# Photodiode_AFE.net
KiCad netlist of a schematic drawn in Altium Designer
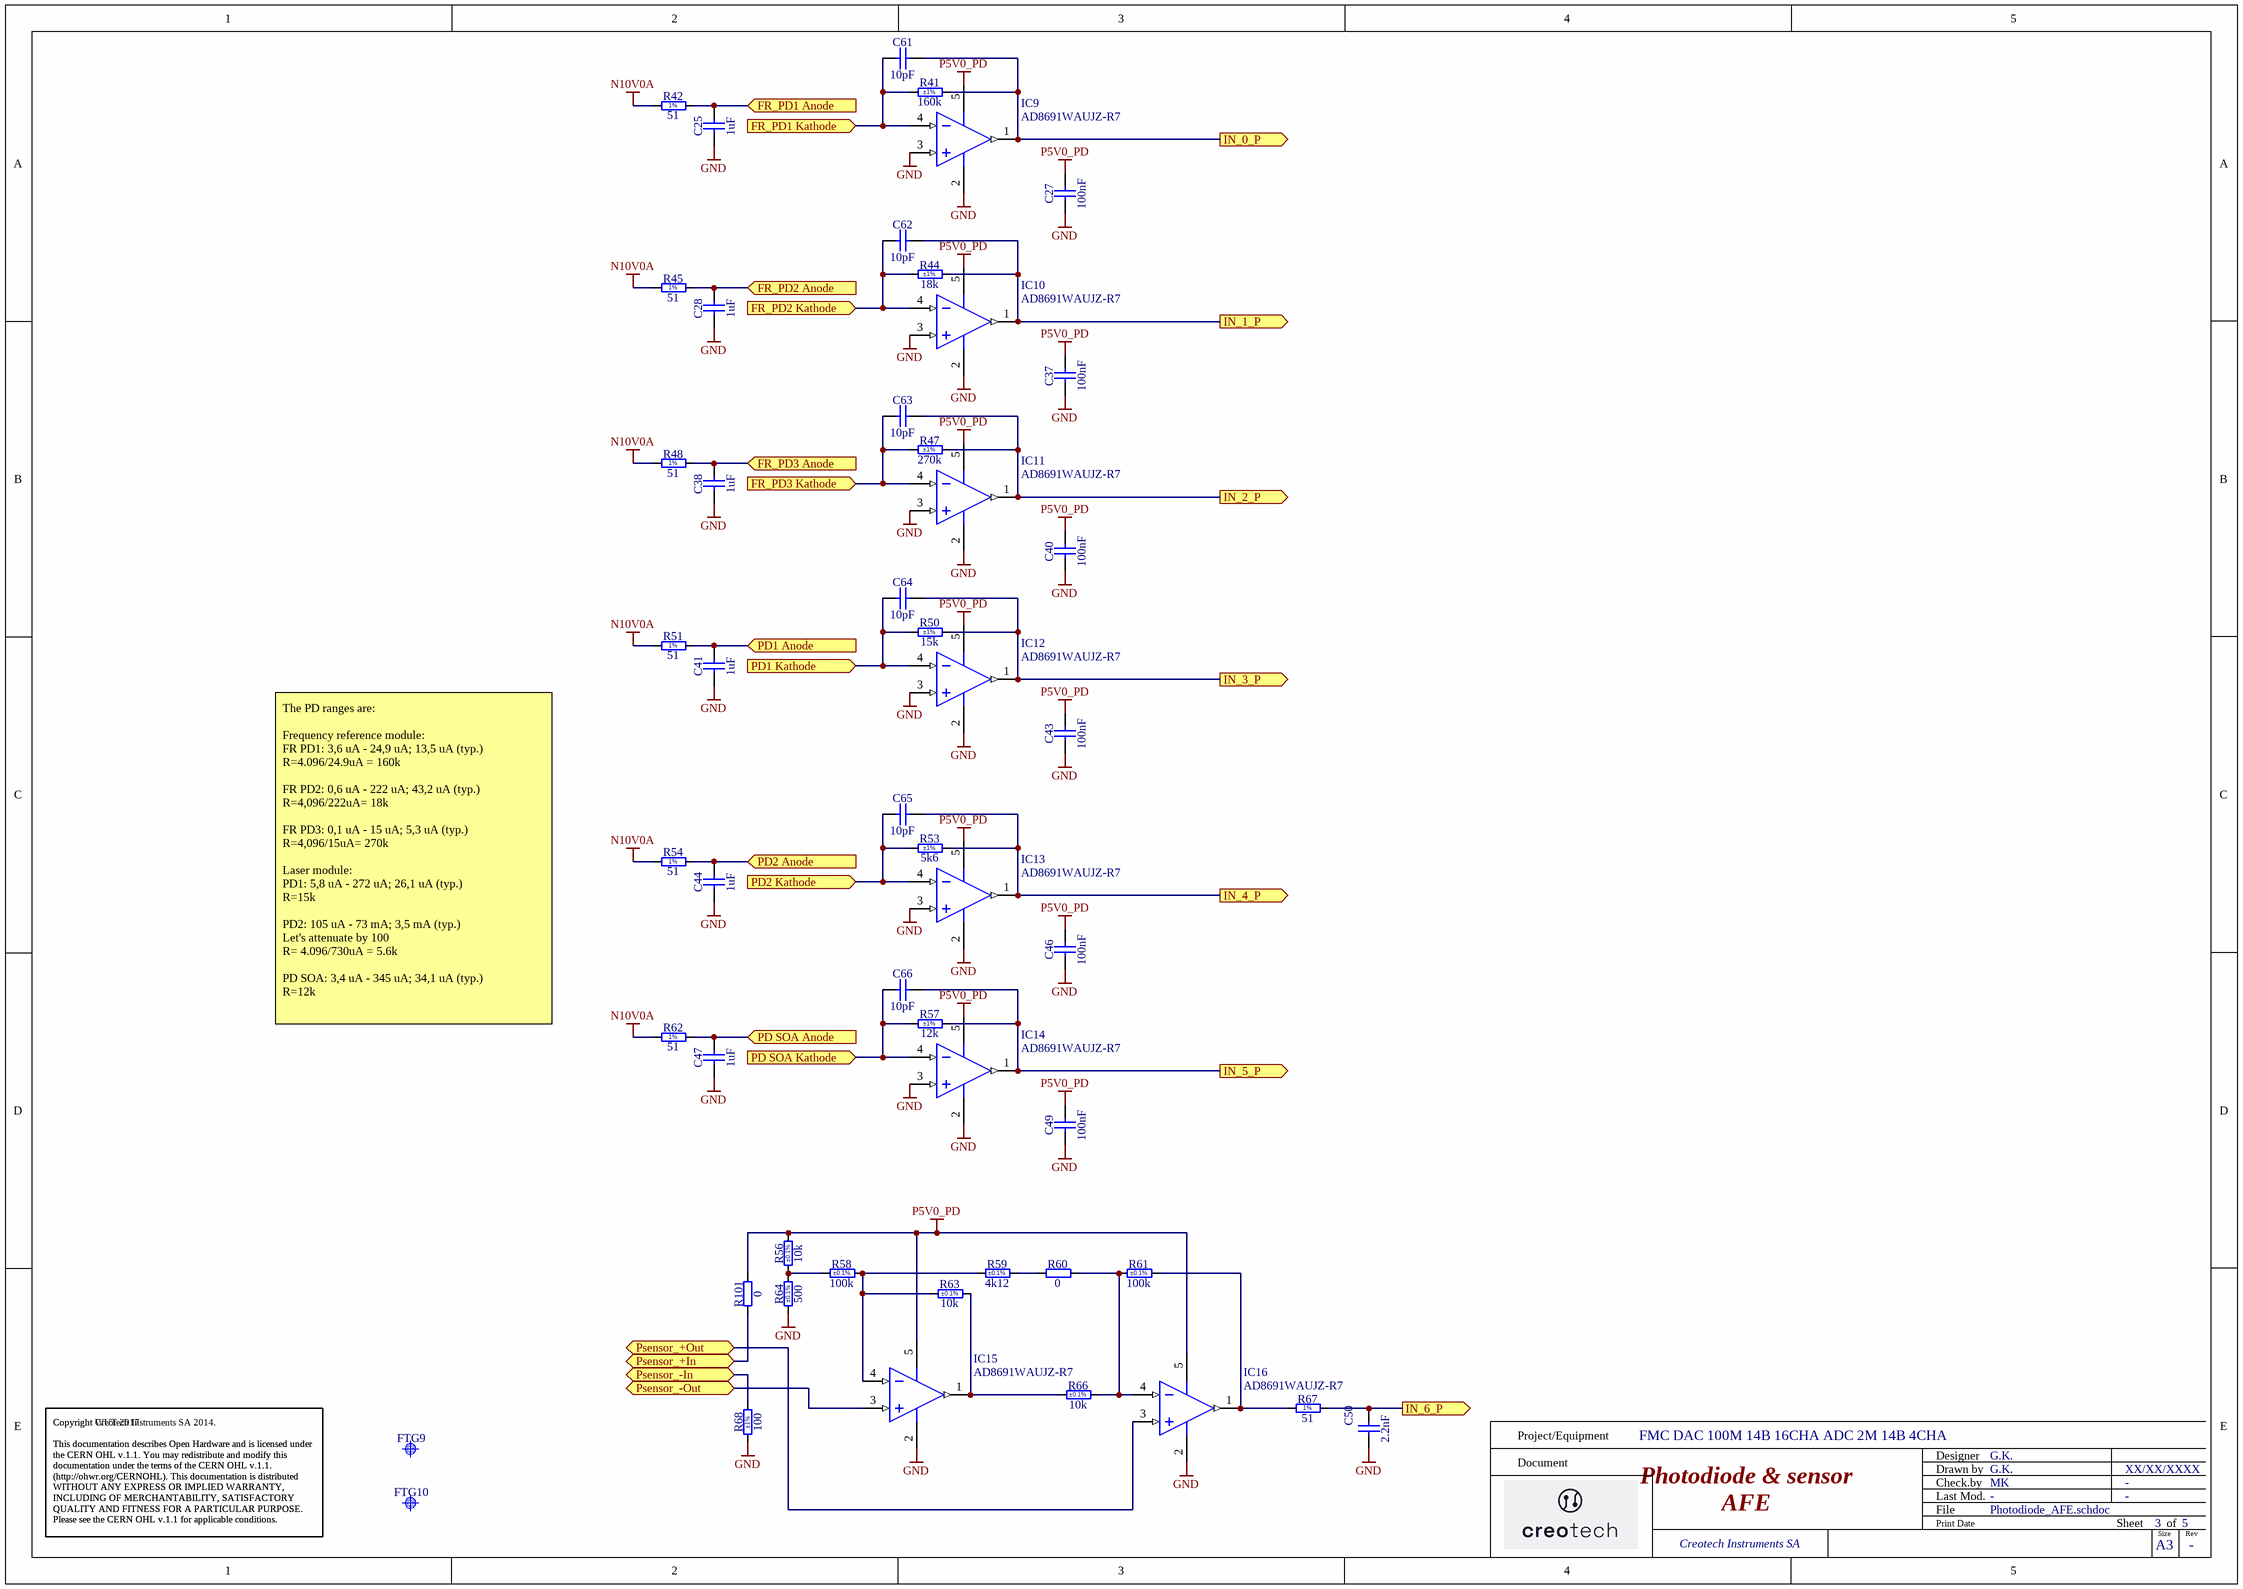
[diagram p0: Photodiode_AFE.schdoc]

(export (version "E")
  (design (tool "Eeschema 10.0.6"))
  (components
    (comp (ref "C25")
      (value "1uF")
      (footprint "CAPC1005X55N")
      (description "Non-polarised capacitor")
      (fields
        (field (name "PART NUMBER") "CC0402_1UF_16V_10%_X5R")
        (field (name "VOLTAGE") "16V")
        (field (name "AUTHOR") "CERN DEM JLC")
      )
      (libsource (lib "Capacitors") (part "Capacitor - non polarized"))
    )
    (comp (ref "C27")
      (value "100nF")
      (footprint "CAPC1005X55N")
      (description "Non-polarised capacitor")
      (fields
        (field (name "PART NUMBER") "CC0402_100NF_16V_10%_X5R")
        (field (name "VOLTAGE") "16V")
        (field (name "AUTHOR") "CERN DEM JLC")
      )
      (libsource (lib "Capacitors") (part "Capacitor - non polarized"))
    )
    (comp (ref "C28")
      (value "1uF")
      (footprint "CAPC1005X55N")
      (description "Non-polarised capacitor")
      (fields
        (field (name "PART NUMBER") "CC0402_1UF_16V_10%_X5R")
        (field (name "VOLTAGE") "16V")
        (field (name "AUTHOR") "CERN DEM JLC")
      )
      (libsource (lib "Capacitors") (part "Capacitor - non polarized"))
    )
    (comp (ref "C37")
      (value "100nF")
      (footprint "CAPC1005X55N")
      (description "Non-polarised capacitor")
      (fields
        (field (name "PART NUMBER") "CC0402_100NF_16V_10%_X5R")
        (field (name "VOLTAGE") "16V")
        (field (name "AUTHOR") "CERN DEM JLC")
      )
      (libsource (lib "Capacitors") (part "Capacitor - non polarized"))
    )
    (comp (ref "C38")
      (value "1uF")
      (footprint "CAPC1005X55N")
      (description "Non-polarised capacitor")
      (fields
        (field (name "PART NUMBER") "CC0402_1UF_16V_10%_X5R")
        (field (name "VOLTAGE") "16V")
        (field (name "AUTHOR") "CERN DEM JLC")
      )
      (libsource (lib "Capacitors") (part "Capacitor - non polarized"))
    )
    (comp (ref "C40")
      (value "100nF")
      (footprint "CAPC1005X55N")
      (description "Non-polarised capacitor")
      (fields
        (field (name "PART NUMBER") "CC0402_100NF_16V_10%_X5R")
        (field (name "VOLTAGE") "16V")
        (field (name "AUTHOR") "CERN DEM JLC")
      )
      (libsource (lib "Capacitors") (part "Capacitor - non polarized"))
    )
    (comp (ref "C41")
      (value "1uF")
      (footprint "CAPC1005X55N")
      (description "Non-polarised capacitor")
      (fields
        (field (name "PART NUMBER") "CC0402_1UF_16V_10%_X5R")
        (field (name "VOLTAGE") "16V")
        (field (name "AUTHOR") "CERN DEM JLC")
      )
      (libsource (lib "Capacitors") (part "Capacitor - non polarized"))
    )
    (comp (ref "C43")
      (value "100nF")
      (footprint "CAPC1005X55N")
      (description "Non-polarised capacitor")
      (fields
        (field (name "PART NUMBER") "CC0402_100NF_16V_10%_X5R")
        (field (name "VOLTAGE") "16V")
        (field (name "AUTHOR") "CERN DEM JLC")
      )
      (libsource (lib "Capacitors") (part "Capacitor - non polarized"))
    )
    (comp (ref "C44")
      (value "1uF")
      (footprint "CAPC1005X55N")
      (description "Non-polarised capacitor")
      (fields
        (field (name "PART NUMBER") "CC0402_1UF_16V_10%_X5R")
        (field (name "VOLTAGE") "16V")
        (field (name "AUTHOR") "CERN DEM JLC")
      )
      (libsource (lib "Capacitors") (part "Capacitor - non polarized"))
    )
    (comp (ref "C46")
      (value "100nF")
      (footprint "CAPC1005X55N")
      (description "Non-polarised capacitor")
      (fields
        (field (name "PART NUMBER") "CC0402_100NF_16V_10%_X5R")
        (field (name "VOLTAGE") "16V")
        (field (name "AUTHOR") "CERN DEM JLC")
      )
      (libsource (lib "Capacitors") (part "Capacitor - non polarized"))
    )
    (comp (ref "C47")
      (value "1uF")
      (footprint "CAPC1005X55N")
      (description "Non-polarised capacitor")
      (fields
        (field (name "PART NUMBER") "CC0402_1UF_16V_10%_X5R")
        (field (name "VOLTAGE") "16V")
        (field (name "AUTHOR") "CERN DEM JLC")
      )
      (libsource (lib "Capacitors") (part "Capacitor - non polarized"))
    )
    (comp (ref "C49")
      (value "100nF")
      (footprint "CAPC1005X55N")
      (description "Non-polarised capacitor")
      (fields
        (field (name "PART NUMBER") "CC0402_100NF_16V_10%_X5R")
        (field (name "VOLTAGE") "16V")
        (field (name "AUTHOR") "CERN DEM JLC")
      )
      (libsource (lib "Capacitors") (part "Capacitor - non polarized"))
    )
    (comp (ref "C50")
      (value "2.2nF")
      (footprint "CAPC2013X100N")
      (description "Non-polarised capacitor")
      (fields
        (field (name "PART NUMBER") "CC0805_2.2NF_25V_1%_C0G")
        (field (name "VOLTAGE") "25V")
        (field (name "AUTHOR") "CERN DEM JLC")
      )
      (libsource (lib "Capacitors") (part "Capacitor - non polarized"))
    )
    (comp (ref "C61")
      (value "10pF")
      (footprint "CAPC1005X55N")
      (description "Non-polarised capacitor")
      (fields
        (field (name "PART NUMBER") "CC0402_10PF_50V_5%_C0G")
        (field (name "VOLTAGE") "50V")
        (field (name "AUTHOR") "CERN DEM JLC")
      )
      (libsource (lib "Capacitors") (part "Capacitor - non polarized"))
    )
    (comp (ref "C62")
      (value "10pF")
      (footprint "CAPC1005X55N")
      (description "Non-polarised capacitor")
      (fields
        (field (name "PART NUMBER") "CC0402_10PF_50V_5%_C0G")
        (field (name "VOLTAGE") "50V")
        (field (name "AUTHOR") "CERN DEM JLC")
      )
      (libsource (lib "Capacitors") (part "Capacitor - non polarized"))
    )
    (comp (ref "C63")
      (value "10pF")
      (footprint "CAPC1005X55N")
      (description "Non-polarised capacitor")
      (fields
        (field (name "PART NUMBER") "CC0402_10PF_50V_5%_C0G")
        (field (name "VOLTAGE") "50V")
        (field (name "AUTHOR") "CERN DEM JLC")
      )
      (libsource (lib "Capacitors") (part "Capacitor - non polarized"))
    )
    (comp (ref "C64")
      (value "10pF")
      (footprint "CAPC1005X55N")
      (description "Non-polarised capacitor")
      (fields
        (field (name "PART NUMBER") "CC0402_10PF_50V_5%_C0G")
        (field (name "VOLTAGE") "50V")
        (field (name "AUTHOR") "CERN DEM JLC")
      )
      (libsource (lib "Capacitors") (part "Capacitor - non polarized"))
    )
    (comp (ref "C65")
      (value "10pF")
      (footprint "CAPC1005X55N")
      (description "Non-polarised capacitor")
      (fields
        (field (name "PART NUMBER") "CC0402_10PF_50V_5%_C0G")
        (field (name "VOLTAGE") "50V")
        (field (name "AUTHOR") "CERN DEM JLC")
      )
      (libsource (lib "Capacitors") (part "Capacitor - non polarized"))
    )
    (comp (ref "C66")
      (value "10pF")
      (footprint "CAPC1005X55N")
      (description "Non-polarised capacitor")
      (fields
        (field (name "PART NUMBER") "CC0402_10PF_50V_5%_C0G")
        (field (name "VOLTAGE") "50V")
        (field (name "AUTHOR") "CERN DEM JLC")
      )
      (libsource (lib "Capacitors") (part "Capacitor - non polarized"))
    )
    (comp (ref "FTG9")
      (value "Use only in PCB")
      (footprint "FIDUCIAL_TOP_C100-200")
      (description "Fiducial Target")
      (fields (field (name "PART NUMBER") "FIDUCIAL_TARGET_C100-200") (field (name "AUTHOR") "CERN DEM JLC"))
      (libsource (lib "Eletro-mechanical") (part "Fiducial Target"))
    )
    (comp (ref "FTG10")
      (value "Use only in PCB")
      (footprint "FIDUCIAL_TOP_S100-200")
      (description "Fiducial Target")
      (fields (field (name "PART NUMBER") "FIDUCIAL_TARGET_S100-200") (field (name "AUTHOR") "CERN DEM JLC"))
      (libsource (lib "Eletro-mechanical") (part "Fiducial Target"))
    )
    (comp (ref "IC9")
      (value "AD8691WAUJZ-R7")
      (footprint "ADI-UJ-5_L")
      (fields (field (name "MANUFACTURER") "Analog Devices") (field (name "GENERIC PART NUMBER") "AD8691"))
      (libsource (lib "Altium Content Vault") (part "ADI-AD8605-CB-5_8691-UJ-5"))
    )
    (comp (ref "IC10")
      (value "AD8691WAUJZ-R7")
      (footprint "ADI-UJ-5_L")
      (fields (field (name "MANUFACTURER") "Analog Devices") (field (name "GENERIC PART NUMBER") "AD8691"))
      (libsource (lib "Altium Content Vault") (part "ADI-AD8605-CB-5_8691-UJ-5"))
    )
    (comp (ref "IC11")
      (value "AD8691WAUJZ-R7")
      (footprint "ADI-UJ-5_L")
      (fields (field (name "MANUFACTURER") "Analog Devices") (field (name "GENERIC PART NUMBER") "AD8691"))
      (libsource (lib "Altium Content Vault") (part "ADI-AD8605-CB-5_8691-UJ-5"))
    )
    (comp (ref "IC12")
      (value "AD8691WAUJZ-R7")
      (footprint "ADI-UJ-5_L")
      (fields (field (name "MANUFACTURER") "Analog Devices") (field (name "GENERIC PART NUMBER") "AD8691"))
      (libsource (lib "Altium Content Vault") (part "ADI-AD8605-CB-5_8691-UJ-5"))
    )
    (comp (ref "IC13")
      (value "AD8691WAUJZ-R7")
      (footprint "ADI-UJ-5_L")
      (fields (field (name "MANUFACTURER") "Analog Devices") (field (name "GENERIC PART NUMBER") "AD8691"))
      (libsource (lib "Altium Content Vault") (part "ADI-AD8605-CB-5_8691-UJ-5"))
    )
    (comp (ref "IC14")
      (value "AD8691WAUJZ-R7")
      (footprint "ADI-UJ-5_L")
      (fields (field (name "MANUFACTURER") "Analog Devices") (field (name "GENERIC PART NUMBER") "AD8691"))
      (libsource (lib "Altium Content Vault") (part "ADI-AD8605-CB-5_8691-UJ-5"))
    )
    (comp (ref "IC15")
      (value "AD8691WAUJZ-R7")
      (footprint "ADI-UJ-5_L")
      (fields (field (name "MANUFACTURER") "Analog Devices") (field (name "GENERIC PART NUMBER") "AD8691"))
      (libsource (lib "Altium Content Vault") (part "ADI-AD8605-CB-5_8691-UJ-5"))
    )
    (comp (ref "IC16")
      (value "AD8691WAUJZ-R7")
      (footprint "ADI-UJ-5_L")
      (fields (field (name "MANUFACTURER") "Analog Devices") (field (name "GENERIC PART NUMBER") "AD8691"))
      (libsource (lib "Altium Content Vault") (part "ADI-AD8605-CB-5_8691-UJ-5"))
    )
    (comp (ref "R41")
      (value "160k")
      (footprint "RESC1608X55N")
      (description "Resistor - 1%")
      (fields
        (field (name "TOLERANCE") "±1%")
        (field (name "PART NUMBER") "R0603_160K_1%_0.1W_100PPM")
        (field (name "POWER") "0.1W")
        (field (name "AUTHOR") "CERN DEM JLC")
      )
      (libsource (lib "") (part "Resistor - 1%_1"))
    )
    (comp (ref "R42")
      (value "51")
      (footprint "RESC1005X40N")
      (description "Resistor - 1%")
      (fields
        (field (name "PART NUMBER") "R0402_51R_1%_0.0625W_100PPM")
        (field (name "POWER") "0.0625W")
        (field (name "AUTHOR") "CERN DEM JLC")
      )
      (libsource (lib "Resistors") (part "Resistor - 1%"))
    )
    (comp (ref "R44")
      (value "18k")
      (footprint "RESC1608X55N")
      (description "Resistor - 1%")
      (fields
        (field (name "TOLERANCE") "±1%")
        (field (name "PART NUMBER") "R0603_18K_1%_0.1W_100PPM")
        (field (name "POWER") "0.1W")
        (field (name "AUTHOR") "CERN DEM JLC")
      )
      (libsource (lib "") (part "Resistor - 1%_1"))
    )
    (comp (ref "R45")
      (value "51")
      (footprint "RESC1005X40N")
      (description "Resistor - 1%")
      (fields
        (field (name "PART NUMBER") "R0402_51R_1%_0.0625W_100PPM")
        (field (name "POWER") "0.0625W")
        (field (name "AUTHOR") "CERN DEM JLC")
      )
      (libsource (lib "Resistors") (part "Resistor - 1%"))
    )
    (comp (ref "R47")
      (value "270k")
      (footprint "RESC1608X55N")
      (description "Resistor - 1%")
      (fields
        (field (name "TOLERANCE") "±1%")
        (field (name "PART NUMBER") "R0603_270K_1%_0.1W_100PPM")
        (field (name "POWER") "0.1W")
        (field (name "AUTHOR") "CERN DEM JLC")
      )
      (libsource (lib "") (part "Resistor - 1%_1"))
    )
    (comp (ref "R48")
      (value "51")
      (footprint "RESC1005X40N")
      (description "Resistor - 1%")
      (fields
        (field (name "PART NUMBER") "R0402_51R_1%_0.0625W_100PPM")
        (field (name "POWER") "0.0625W")
        (field (name "AUTHOR") "CERN DEM JLC")
      )
      (libsource (lib "Resistors") (part "Resistor - 1%"))
    )
    (comp (ref "R50")
      (value "15k")
      (footprint "RESC1608X55N")
      (description "Resistor - 1%")
      (fields
        (field (name "TOLERANCE") "±1%")
        (field (name "PART NUMBER") "R0603_15K_1%_0.1W_100PPM")
        (field (name "POWER") "0.1W")
        (field (name "AUTHOR") "CERN DEM JMW")
      )
      (libsource (lib "") (part "Resistor - 1%_1"))
    )
    (comp (ref "R51")
      (value "51")
      (footprint "RESC1005X40N")
      (description "Resistor - 1%")
      (fields
        (field (name "PART NUMBER") "R0402_51R_1%_0.0625W_100PPM")
        (field (name "POWER") "0.0625W")
        (field (name "AUTHOR") "CERN DEM JLC")
      )
      (libsource (lib "Resistors") (part "Resistor - 1%"))
    )
    (comp (ref "R53")
      (value "5k6")
      (footprint "RESC1608X55N")
      (description "Resistor - 1%")
      (fields
        (field (name "TOLERANCE") "±1%")
        (field (name "PART NUMBER") "R0603_5K6_1%_0.125W_100PPM")
        (field (name "POWER") "0.125W")
        (field (name "AUTHOR") "CERN DEM WB")
      )
      (libsource (lib "") (part "Resistor - 1%_1"))
    )
    (comp (ref "R54")
      (value "51")
      (footprint "RESC1005X40N")
      (description "Resistor - 1%")
      (fields
        (field (name "PART NUMBER") "R0402_51R_1%_0.0625W_100PPM")
        (field (name "POWER") "0.0625W")
        (field (name "AUTHOR") "CERN DEM JLC")
      )
      (libsource (lib "Resistors") (part "Resistor - 1%"))
    )
    (comp (ref "R56")
      (value "10k")
      (footprint "RESC1608X64N")
      (description "Resistor - 0.1%")
      (fields
        (field (name "TOLERANCE") "±0.1%")
        (field (name "PART NUMBER") "R0603_10K_0.1%_0.1W_25PPM")
        (field (name "POWER") "0.1W")
        (field (name "AUTHOR") "CERN DEM JMW")
      )
      (libsource (lib "Resistors") (part "Resistor - 0.1%"))
    )
    (comp (ref "R57")
      (value "12k")
      (footprint "RESC1608X55N")
      (description "Resistor - 1%")
      (fields
        (field (name "TOLERANCE") "±1%")
        (field (name "PART NUMBER") "R0603_12K_1%_0.1W_100PPM")
        (field (name "POWER") "0.1W")
        (field (name "AUTHOR") "CERN DEM JLC")
      )
      (libsource (lib "") (part "Resistor - 1%_1"))
    )
    (comp (ref "R58")
      (value "100k")
      (footprint "RESC1608X55N")
      (description "Resistor - 0.1%")
      (fields
        (field (name "TOLERANCE") "±0.1%")
        (field (name "PART NUMBER") "R0603_100K_0.1%_0.063W_10PPM")
        (field (name "POWER") "0.063W")
        (field (name "AUTHOR") "CERN DEM JLC")
      )
      (libsource (lib "Resistors") (part "Resistor - 0.1%"))
    )
    (comp (ref "R59")
      (value "4k12")
      (footprint "RESC1608X55N")
      (description "Resistor - 0.1%")
      (fields
        (field (name "TOLERANCE") "±0.1%")
        (field (name "PART NUMBER") "R0603_4K12_0.1%_0.063W_10PPM")
        (field (name "POWER") "0.063W")
        (field (name "AUTHOR") "CERN DEM JLC")
      )
      (libsource (lib "Resistors") (part "Resistor - 0.1%"))
    )
    (comp (ref "R60")
      (value "0")
      (footprint "RESC1608X55N")
      (description "Resistor")
      (fields
        (field (name "PART NUMBER") "R0603_0R_JUMPER")
        (field (name "MANUFACTURER") "GENERIC")
        (field (name "AUTHOR") "CERN DEM JLC")
      )
      (libsource (lib "Resistors") (part "Resistor"))
    )
    (comp (ref "R61")
      (value "100k")
      (footprint "RESC1608X55N")
      (description "Resistor - 0.1%")
      (fields
        (field (name "TOLERANCE") "±0.1%")
        (field (name "PART NUMBER") "R0603_100K_0.1%_0.063W_10PPM")
        (field (name "POWER") "0.063W")
        (field (name "AUTHOR") "CERN DEM JLC")
      )
      (libsource (lib "Resistors") (part "Resistor - 0.1%"))
    )
    (comp (ref "R62")
      (value "51")
      (footprint "RESC1005X40N")
      (description "Resistor - 1%")
      (fields
        (field (name "PART NUMBER") "R0402_51R_1%_0.0625W_100PPM")
        (field (name "POWER") "0.0625W")
        (field (name "AUTHOR") "CERN DEM JLC")
      )
      (libsource (lib "Resistors") (part "Resistor - 1%"))
    )
    (comp (ref "R63")
      (value "10k")
      (footprint "RESC1608X64N")
      (description "Resistor - 0.1%")
      (fields
        (field (name "TOLERANCE") "±0.1%")
        (field (name "PART NUMBER") "R0603_10K_0.1%_0.1W_25PPM")
        (field (name "POWER") "0.1W")
        (field (name "AUTHOR") "CERN DEM JMW")
      )
      (libsource (lib "Resistors") (part "Resistor - 0.1%"))
    )
    (comp (ref "R64")
      (value "500")
      (footprint "RESC1106X84N")
      (description "Resistor - 0.1%")
      (fields
        (field (name "TOLERANCE") "±0.1%")
        (field (name "PART NUMBER") "R0402_500R_0.1%_0.05W_25PPM_VISHAY_PNM")
        (field (name "POWER") "0.05W")
        (field (name "AUTHOR") "CERN DEM JLC")
      )
      (libsource (lib "Resistors") (part "Resistor - 0.1%"))
    )
    (comp (ref "R66")
      (value "10k")
      (footprint "RESC1608X64N")
      (description "Resistor - 0.1%")
      (fields
        (field (name "TOLERANCE") "±0.1%")
        (field (name "PART NUMBER") "R0603_10K_0.1%_0.1W_25PPM")
        (field (name "POWER") "0.1W")
        (field (name "AUTHOR") "CERN DEM JMW")
      )
      (libsource (lib "Resistors") (part "Resistor - 0.1%"))
    )
    (comp (ref "R67")
      (value "51")
      (footprint "RESC1005X40N")
      (description "Resistor - 1%")
      (fields
        (field (name "PART NUMBER") "R0402_51R_1%_0.0625W_100PPM")
        (field (name "POWER") "0.0625W")
        (field (name "AUTHOR") "CERN DEM JLC")
      )
      (libsource (lib "Resistors") (part "Resistor - 1%"))
    )
    (comp (ref "R68")
      (value "100")
      (footprint "RESC1005X40N")
      (description "Resistor - 1%")
      (fields
        (field (name "TOLERANCE") "±1%")
        (field (name "PART NUMBER") "R0402_100R_1%_0.0625W_100PPM")
        (field (name "POWER") "0.0625W")
        (field (name "AUTHOR") "CERN DEM JLC")
      )
      (libsource (lib "") (part "Resistor - 1%_1"))
    )
    (comp (ref "R101")
      (value "0")
      (footprint "RESC1608X55N")
      (description "Resistor")
      (fields
        (field (name "PART NUMBER") "R0603_0R_JUMPER")
        (field (name "MANUFACTURER") "GENERIC")
        (field (name "AUTHOR") "CERN DEM JLC")
      )
      (libsource (lib "Resistors") (part "Resistor"))
    )
  )
  (nets
    (net (code "1") (name "/FR_PD1 Anode") (class "Default")
      (node (ref "C25") (pin "2") (pinfunction "2_2") (pintype "passive"))
      (node (ref "R42") (pin "2") (pinfunction "2_2") (pintype "passive"))
    )
    (net (code "2") (name "/FR_PD1 Kathode") (class "Default")
      (node (ref "C61") (pin "1") (pinfunction "1_1") (pintype "passive"))
      (node (ref "IC9") (pin "4") (pinfunction "-IN_4") (pintype "input"))
      (node (ref "R41") (pin "1") (pinfunction "1_1") (pintype "passive"))
    )
    (net (code "3") (name "/FR_PD2 Anode") (class "Default")
      (node (ref "C28") (pin "2") (pinfunction "2_2") (pintype "passive"))
      (node (ref "R45") (pin "2") (pinfunction "2_2") (pintype "passive"))
    )
    (net (code "4") (name "/FR_PD2 Kathode") (class "Default")
      (node (ref "C62") (pin "1") (pinfunction "1_1") (pintype "passive"))
      (node (ref "IC10") (pin "4") (pinfunction "-IN_4") (pintype "input"))
      (node (ref "R44") (pin "1") (pinfunction "1_1") (pintype "passive"))
    )
    (net (code "5") (name "/FR_PD3 Anode") (class "Default")
      (node (ref "C38") (pin "2") (pinfunction "2_2") (pintype "passive"))
      (node (ref "R48") (pin "2") (pinfunction "2_2") (pintype "passive"))
    )
    (net (code "6") (name "/FR_PD3 Kathode") (class "Default")
      (node (ref "C63") (pin "1") (pinfunction "1_1") (pintype "passive"))
      (node (ref "IC11") (pin "4") (pinfunction "-IN_4") (pintype "input"))
      (node (ref "R47") (pin "1") (pinfunction "1_1") (pintype "passive"))
    )
    (net (code "7") (name "/IN_0_P") (class "Default")
      (node (ref "C61") (pin "2") (pinfunction "2_2") (pintype "passive"))
      (node (ref "IC9") (pin "1") (pinfunction "OUT_1") (pintype "output"))
      (node (ref "R41") (pin "2") (pinfunction "2_2") (pintype "passive"))
    )
    (net (code "8") (name "/IN_1_P") (class "Default")
      (node (ref "C62") (pin "2") (pinfunction "2_2") (pintype "passive"))
      (node (ref "IC10") (pin "1") (pinfunction "OUT_1") (pintype "output"))
      (node (ref "R44") (pin "2") (pinfunction "2_2") (pintype "passive"))
    )
    (net (code "9") (name "/IN_2_P") (class "Default")
      (node (ref "C63") (pin "2") (pinfunction "2_2") (pintype "passive"))
      (node (ref "IC11") (pin "1") (pinfunction "OUT_1") (pintype "output"))
      (node (ref "R47") (pin "2") (pinfunction "2_2") (pintype "passive"))
    )
    (net (code "10") (name "/IN_3_P") (class "Default")
      (node (ref "C64") (pin "2") (pinfunction "2_2") (pintype "passive"))
      (node (ref "IC12") (pin "1") (pinfunction "OUT_1") (pintype "output"))
      (node (ref "R50") (pin "2") (pinfunction "2_2") (pintype "passive"))
    )
    (net (code "11") (name "/IN_4_P") (class "Default")
      (node (ref "C65") (pin "2") (pinfunction "2_2") (pintype "passive"))
      (node (ref "IC13") (pin "1") (pinfunction "OUT_1") (pintype "output"))
      (node (ref "R53") (pin "2") (pinfunction "2_2") (pintype "passive"))
    )
    (net (code "12") (name "/IN_5_P") (class "Default")
      (node (ref "C66") (pin "2") (pinfunction "2_2") (pintype "passive"))
      (node (ref "IC14") (pin "1") (pinfunction "OUT_1") (pintype "output"))
      (node (ref "R57") (pin "2") (pinfunction "2_2") (pintype "passive"))
    )
    (net (code "13") (name "/IN_6_P") (class "Default")
      (node (ref "C50") (pin "2") (pinfunction "2_2") (pintype "passive"))
      (node (ref "R67") (pin "2") (pinfunction "2_2") (pintype "passive"))
    )
    (net (code "14") (name "/PD SOA Anode") (class "Default")
      (node (ref "C47") (pin "2") (pinfunction "2_2") (pintype "passive"))
      (node (ref "R62") (pin "2") (pinfunction "2_2") (pintype "passive"))
    )
    (net (code "15") (name "/PD SOA Kathode") (class "Default")
      (node (ref "C66") (pin "1") (pinfunction "1_1") (pintype "passive"))
      (node (ref "IC14") (pin "4") (pinfunction "-IN_4") (pintype "input"))
      (node (ref "R57") (pin "1") (pinfunction "1_1") (pintype "passive"))
    )
    (net (code "16") (name "/PD1 Anode") (class "Default")
      (node (ref "C41") (pin "2") (pinfunction "2_2") (pintype "passive"))
      (node (ref "R51") (pin "2") (pinfunction "2_2") (pintype "passive"))
    )
    (net (code "17") (name "/PD1 Kathode") (class "Default")
      (node (ref "C64") (pin "1") (pinfunction "1_1") (pintype "passive"))
      (node (ref "IC12") (pin "4") (pinfunction "-IN_4") (pintype "input"))
      (node (ref "R50") (pin "1") (pinfunction "1_1") (pintype "passive"))
    )
    (net (code "18") (name "/PD2 Anode") (class "Default")
      (node (ref "C44") (pin "2") (pinfunction "2_2") (pintype "passive"))
      (node (ref "R54") (pin "2") (pinfunction "2_2") (pintype "passive"))
    )
    (net (code "19") (name "/PD2 Kathode") (class "Default")
      (node (ref "C65") (pin "1") (pinfunction "1_1") (pintype "passive"))
      (node (ref "IC13") (pin "4") (pinfunction "-IN_4") (pintype "input"))
      (node (ref "R53") (pin "1") (pinfunction "1_1") (pintype "passive"))
    )
    (net (code "20") (name "/Psensor_+In") (class "Default")
      (node (ref "R101") (pin "1") (pinfunction "1_1") (pintype "passive"))
    )
    (net (code "21") (name "/Psensor_+Out") (class "Default")
      (node (ref "IC16") (pin "3") (pinfunction "+IN_3") (pintype "input"))
    )
    (net (code "22") (name "/Psensor_-In") (class "Default")
      (node (ref "R68") (pin "2") (pinfunction "2_2") (pintype "passive"))
    )
    (net (code "23") (name "/Psensor_-Out") (class "Default")
      (node (ref "IC15") (pin "3") (pinfunction "+IN_3") (pintype "input"))
    )
    (net (code "24") (name "GND") (class "Default")
      (node (ref "C25") (pin "1") (pinfunction "1_1") (pintype "passive"))
      (node (ref "C27") (pin "1") (pinfunction "1_1") (pintype "passive"))
      (node (ref "C28") (pin "1") (pinfunction "1_1") (pintype "passive"))
      (node (ref "C37") (pin "1") (pinfunction "1_1") (pintype "passive"))
      (node (ref "C38") (pin "1") (pinfunction "1_1") (pintype "passive"))
      (node (ref "C40") (pin "1") (pinfunction "1_1") (pintype "passive"))
      (node (ref "C41") (pin "1") (pinfunction "1_1") (pintype "passive"))
      (node (ref "C43") (pin "1") (pinfunction "1_1") (pintype "passive"))
      (node (ref "C44") (pin "1") (pinfunction "1_1") (pintype "passive"))
      (node (ref "C46") (pin "1") (pinfunction "1_1") (pintype "passive"))
      (node (ref "C47") (pin "1") (pinfunction "1_1") (pintype "passive"))
      (node (ref "C49") (pin "1") (pinfunction "1_1") (pintype "passive"))
      (node (ref "C50") (pin "1") (pinfunction "1_1") (pintype "passive"))
      (node (ref "IC10") (pin "2") (pinfunction "-V_2") (pintype "power_in"))
      (node (ref "IC10") (pin "3") (pinfunction "+IN_3") (pintype "input"))
      (node (ref "IC11") (pin "2") (pinfunction "-V_2") (pintype "power_in"))
      (node (ref "IC11") (pin "3") (pinfunction "+IN_3") (pintype "input"))
      (node (ref "IC12") (pin "2") (pinfunction "-V_2") (pintype "power_in"))
      (node (ref "IC12") (pin "3") (pinfunction "+IN_3") (pintype "input"))
      (node (ref "IC13") (pin "2") (pinfunction "-V_2") (pintype "power_in"))
      (node (ref "IC13") (pin "3") (pinfunction "+IN_3") (pintype "input"))
      (node (ref "IC14") (pin "2") (pinfunction "-V_2") (pintype "power_in"))
      (node (ref "IC14") (pin "3") (pinfunction "+IN_3") (pintype "input"))
      (node (ref "IC15") (pin "2") (pinfunction "-V_2") (pintype "power_in"))
      (node (ref "IC16") (pin "2") (pinfunction "-V_2") (pintype "power_in"))
      (node (ref "IC9") (pin "2") (pinfunction "-V_2") (pintype "power_in"))
      (node (ref "IC9") (pin "3") (pinfunction "+IN_3") (pintype "input"))
      (node (ref "R64") (pin "1") (pinfunction "1_1") (pintype "passive"))
      (node (ref "R68") (pin "1") (pinfunction "1_1") (pintype "passive"))
    )
    (net (code "25") (name "N10V0A") (class "Default")
      (node (ref "R42") (pin "1") (pinfunction "1_1") (pintype "passive"))
      (node (ref "R45") (pin "1") (pinfunction "1_1") (pintype "passive"))
      (node (ref "R48") (pin "1") (pinfunction "1_1") (pintype "passive"))
      (node (ref "R51") (pin "1") (pinfunction "1_1") (pintype "passive"))
      (node (ref "R54") (pin "1") (pinfunction "1_1") (pintype "passive"))
      (node (ref "R62") (pin "1") (pinfunction "1_1") (pintype "passive"))
    )
    (net (code "26") (name "Net-(IC15--IN)") (class "Default")
      (node (ref "IC15") (pin "4") (pinfunction "-IN_4") (pintype "input"))
      (node (ref "R58") (pin "2") (pinfunction "2_2") (pintype "passive"))
      (node (ref "R59") (pin "1") (pinfunction "1_1") (pintype "passive"))
      (node (ref "R63") (pin "1") (pinfunction "1_1") (pintype "passive"))
    )
    (net (code "27") (name "Net-(IC15-OUT)") (class "Default")
      (node (ref "IC15") (pin "1") (pinfunction "OUT_1") (pintype "output"))
      (node (ref "R63") (pin "2") (pinfunction "2_2") (pintype "passive"))
      (node (ref "R66") (pin "1") (pinfunction "1_1") (pintype "passive"))
    )
    (net (code "28") (name "Net-(IC16--IN)") (class "Default")
      (node (ref "IC16") (pin "4") (pinfunction "-IN_4") (pintype "input"))
      (node (ref "R60") (pin "2") (pinfunction "2_2") (pintype "passive"))
      (node (ref "R61") (pin "1") (pinfunction "1_1") (pintype "passive"))
      (node (ref "R66") (pin "2") (pinfunction "2_2") (pintype "passive"))
    )
    (net (code "29") (name "Net-(IC16-OUT)") (class "Default")
      (node (ref "IC16") (pin "1") (pinfunction "OUT_1") (pintype "output"))
      (node (ref "R61") (pin "2") (pinfunction "2_2") (pintype "passive"))
      (node (ref "R67") (pin "1") (pinfunction "1_1") (pintype "passive"))
    )
    (net (code "30") (name "Net-(R56-Pad1)") (class "Default")
      (node (ref "R56") (pin "1") (pinfunction "1_1") (pintype "passive"))
      (node (ref "R58") (pin "1") (pinfunction "1_1") (pintype "passive"))
      (node (ref "R64") (pin "2") (pinfunction "2_2") (pintype "passive"))
    )
    (net (code "31") (name "Net-(R59-Pad2)") (class "Default")
      (node (ref "R59") (pin "2") (pinfunction "2_2") (pintype "passive"))
      (node (ref "R60") (pin "1") (pinfunction "1_1") (pintype "passive"))
    )
    (net (code "32") (name "P5V0_PD") (class "Default")
      (node (ref "C27") (pin "2") (pinfunction "2_2") (pintype "passive"))
      (node (ref "C37") (pin "2") (pinfunction "2_2") (pintype "passive"))
      (node (ref "C40") (pin "2") (pinfunction "2_2") (pintype "passive"))
      (node (ref "C43") (pin "2") (pinfunction "2_2") (pintype "passive"))
      (node (ref "C46") (pin "2") (pinfunction "2_2") (pintype "passive"))
      (node (ref "C49") (pin "2") (pinfunction "2_2") (pintype "passive"))
      (node (ref "IC10") (pin "5") (pinfunction "+V_5") (pintype "power_in"))
      (node (ref "IC11") (pin "5") (pinfunction "+V_5") (pintype "power_in"))
      (node (ref "IC12") (pin "5") (pinfunction "+V_5") (pintype "power_in"))
      (node (ref "IC13") (pin "5") (pinfunction "+V_5") (pintype "power_in"))
      (node (ref "IC14") (pin "5") (pinfunction "+V_5") (pintype "power_in"))
      (node (ref "IC15") (pin "5") (pinfunction "+V_5") (pintype "power_in"))
      (node (ref "IC16") (pin "5") (pinfunction "+V_5") (pintype "power_in"))
      (node (ref "IC9") (pin "5") (pinfunction "+V_5") (pintype "power_in"))
      (node (ref "R101") (pin "2") (pinfunction "2_2") (pintype "passive"))
      (node (ref "R56") (pin "2") (pinfunction "2_2") (pintype "passive"))
    )
  )
)
